# TubesMagangURO.net
KiCad netlist of a schematic drawn in Altium Designer
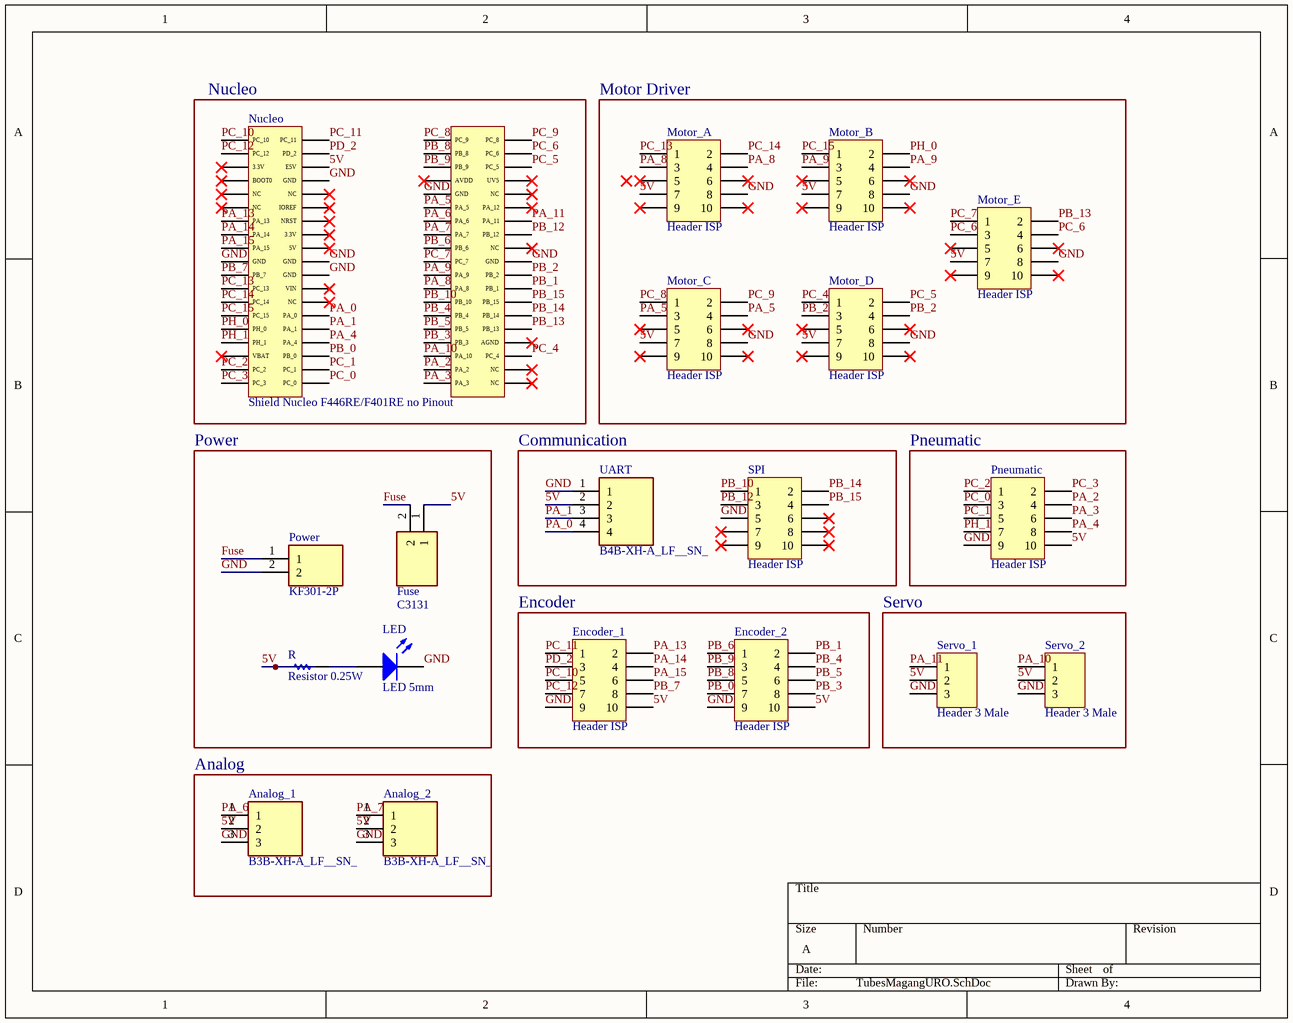
[diagram p0: TubesMagangURO.SchDoc]

(export (version "E")
  (design (tool "Eeschema 10.0.6"))
  (components
    (comp (ref "Analog_1")
      (value "B3B-XH-A_LF__SN_")
      (footprint "B3BXHALFSN")
      (description "Connector")
      (fields (field (name "MANUFACTURER_PART_NUMBER") "B3B-XH-A(LF)(SN)"))
      (libsource (lib "SamacSys") (part "B3B-XH-A_LF__SN_"))
    )
    (comp (ref "Analog_2")
      (value "B3B-XH-A_LF__SN_")
      (footprint "B3BXHALFSN")
      (description "Connector")
      (fields (field (name "MANUFACTURER_PART_NUMBER") "B3B-XH-A(LF)(SN)"))
      (libsource (lib "SamacSys") (part "B3B-XH-A_LF__SN_"))
    )
    (comp (ref "Encoder_1")
      (value "Header ISP")
      (footprint "Header ISP")
      (libsource (lib "GAPlib_CONNECTOR") (part "Header ISP"))
    )
    (comp (ref "Encoder_2")
      (value "Header ISP")
      (footprint "Header ISP")
      (libsource (lib "GAPlib_CONNECTOR") (part "Header ISP"))
    )
    (comp (ref "Fuse")
      (value "C3131")
      (footprint "SamacSys:C3131")
      (description "Undefined or Miscellaneous")
      (libsource (lib "*") (part "C3131"))
    )
    (comp (ref "LED")
      (value "LED 5mm")
      (footprint "LED 5mm")
      (libsource (lib "GAPlib_DEVICES") (part "LED 5mm"))
    )
    (comp (ref "Motor_A")
      (value "Header ISP")
      (footprint "Header ISP")
      (libsource (lib "GAPlib_CONNECTOR") (part "Header ISP"))
    )
    (comp (ref "Motor_B")
      (value "Header ISP")
      (footprint "Header ISP")
      (libsource (lib "GAPlib_CONNECTOR") (part "Header ISP"))
    )
    (comp (ref "Motor_C")
      (value "Header ISP")
      (footprint "Header ISP")
      (libsource (lib "GAPlib_CONNECTOR") (part "Header ISP"))
    )
    (comp (ref "Motor_D")
      (value "Header ISP")
      (footprint "Header ISP")
      (libsource (lib "GAPlib_CONNECTOR") (part "Header ISP"))
    )
    (comp (ref "Motor_E")
      (value "Header ISP")
      (footprint "Header ISP")
      (libsource (lib "GAPlib_CONNECTOR") (part "Header ISP"))
    )
    (comp (ref "Nucleo")
      (value "Shield Nucleo F446RE/F401RE no Pinout")
      (footprint "Shield Nucleo-F446RE/F401RE-tanpaPinOut")
      (description "Tanpa Pinout")
      (libsource (lib "GAPlib_SHIELD") (part "Shield Nucleo-F446RE/F401RE-tanpa Pinout"))
    )
    (comp (ref "Pneumatic")
      (value "Header ISP")
      (footprint "Header ISP")
      (libsource (lib "GAPlib_CONNECTOR") (part "Header ISP"))
    )
    (comp (ref "Power")
      (value "KF301-2P")
      (footprint "KF3012P")
      (description "Connector")
      (libsource (lib "SamacSys") (part "KF301-2P"))
    )
    (comp (ref "R")
      (value "Resistor 0.25W")
      (footprint "Resistor 0.25W")
      (libsource (lib "GAPlib_DEVICES") (part "Resistor 0.25W"))
    )
    (comp (ref "Servo_1")
      (value "Header 3 Male")
      (footprint "Header 3 Male")
      (libsource (lib "GAPlib_CONNECTOR") (part "Header 3 Male"))
    )
    (comp (ref "Servo_2")
      (value "Header 3 Male")
      (footprint "Header 3 Male")
      (libsource (lib "GAPlib_CONNECTOR") (part "Header 3 Male"))
    )
    (comp (ref "SPI")
      (value "Header ISP")
      (footprint "Header ISP")
      (libsource (lib "GAPlib_CONNECTOR") (part "Header ISP"))
    )
    (comp (ref "UART")
      (value "B4B-XH-A_LF__SN_")
      (footprint "SamacSys:B4BXHALFSN")
      (description "Connector")
      (fields (field (name "MANUFACTURER_PART_NUMBER") "B4B-XH-A(LF)(SN)"))
      (libsource (lib "SamacSys") (part "B4B-XH-A_LF__SN_"))
    )
  )
  (nets
    (net (code "1") (name "/5V") (class "Default")
      (node (ref "Analog_1") (pin "2") (pinfunction "2_2") (pintype "passive"))
      (node (ref "Analog_2") (pin "2") (pinfunction "2_2") (pintype "passive"))
      (node (ref "Encoder_1") (pin "10") (pinfunction "10_10") (pintype "passive"))
      (node (ref "Encoder_2") (pin "10") (pinfunction "10_10") (pintype "passive"))
      (node (ref "Fuse") (pin "1") (pinfunction "1_1") (pintype "passive"))
      (node (ref "Motor_A") (pin "7") (pinfunction "7_7") (pintype "passive"))
      (node (ref "Motor_B") (pin "7") (pinfunction "7_7") (pintype "passive"))
      (node (ref "Motor_C") (pin "7") (pinfunction "7_7") (pintype "passive"))
      (node (ref "Motor_D") (pin "7") (pinfunction "7_7") (pintype "passive"))
      (node (ref "Motor_E") (pin "7") (pinfunction "7_7") (pintype "passive"))
      (node (ref "Nucleo") (pin "E5V") (pinfunction "E5V_E5V") (pintype "passive"))
      (node (ref "Pneumatic") (pin "10") (pinfunction "10_10") (pintype "passive"))
      (node (ref "R") (pin "1") (pinfunction "1_1") (pintype "passive"))
      (node (ref "Servo_1") (pin "2") (pinfunction "2_2") (pintype "passive"))
      (node (ref "Servo_2") (pin "2") (pinfunction "2_2") (pintype "passive"))
      (node (ref "UART") (pin "2") (pinfunction "2_2") (pintype "passive"))
    )
    (net (code "2") (name "/Fuse") (class "Default")
      (node (ref "Fuse") (pin "2") (pinfunction "2_2") (pintype "passive"))
      (node (ref "Power") (pin "1") (pinfunction "1_1") (pintype "passive"))
    )
    (net (code "3") (name "/GND") (class "Default")
      (node (ref "Analog_1") (pin "3") (pinfunction "3_3") (pintype "passive"))
      (node (ref "Analog_2") (pin "3") (pinfunction "3_3") (pintype "passive"))
      (node (ref "Encoder_1") (pin "9") (pinfunction "9_9") (pintype "passive"))
      (node (ref "Encoder_2") (pin "9") (pinfunction "9_9") (pintype "passive"))
      (node (ref "LED") (pin "2") (pinfunction "K_2") (pintype "passive"))
      (node (ref "Motor_A") (pin "8") (pinfunction "8_8") (pintype "passive"))
      (node (ref "Motor_B") (pin "8") (pinfunction "8_8") (pintype "passive"))
      (node (ref "Motor_C") (pin "8") (pinfunction "8_8") (pintype "passive"))
      (node (ref "Motor_D") (pin "8") (pinfunction "8_8") (pintype "passive"))
      (node (ref "Motor_E") (pin "8") (pinfunction "8_8") (pintype "passive"))
      (node (ref "Nucleo") (pin "GND") (pinfunction "GND_GND") (pintype "passive"))
      (node (ref "Nucleo") (pin "GND1") (pinfunction "GND_GND1") (pintype "passive"))
      (node (ref "Nucleo") (pin "GND2") (pinfunction "GND_GND2") (pintype "passive"))
      (node (ref "Nucleo") (pin "GND3") (pinfunction "GND_GND3") (pintype "passive"))
      (node (ref "Nucleo") (pin "GND4") (pinfunction "GND_GND4") (pintype "passive"))
      (node (ref "Nucleo") (pin "GND5") (pinfunction "GND_GND5") (pintype "passive"))
      (node (ref "Pneumatic") (pin "9") (pinfunction "9_9") (pintype "passive"))
      (node (ref "Power") (pin "2") (pinfunction "2_2") (pintype "passive"))
      (node (ref "SPI") (pin "5") (pinfunction "5_5") (pintype "passive"))
      (node (ref "Servo_1") (pin "3") (pinfunction "3_3") (pintype "passive"))
      (node (ref "Servo_2") (pin "3") (pinfunction "3_3") (pintype "passive"))
      (node (ref "UART") (pin "1") (pinfunction "1_1") (pintype "passive"))
    )
    (net (code "4") (name "/PA_0") (class "Default")
      (node (ref "Nucleo") (pin "PA_0") (pinfunction "PA_0_PA_0") (pintype "passive"))
      (node (ref "UART") (pin "4") (pinfunction "4_4") (pintype "passive"))
    )
    (net (code "5") (name "/PA_1") (class "Default")
      (node (ref "Nucleo") (pin "PA_1") (pinfunction "PA_1_PA_1") (pintype "passive"))
      (node (ref "UART") (pin "3") (pinfunction "3_3") (pintype "passive"))
    )
    (net (code "6") (name "/PA_2") (class "Default")
      (node (ref "Nucleo") (pin "PA_2") (pinfunction "PA_2_PA_2") (pintype "passive"))
      (node (ref "Pneumatic") (pin "4") (pinfunction "4_4") (pintype "passive"))
    )
    (net (code "7") (name "/PA_3") (class "Default")
      (node (ref "Nucleo") (pin "PA_3") (pinfunction "PA_3_PA_3") (pintype "passive"))
      (node (ref "Pneumatic") (pin "6") (pinfunction "6_6") (pintype "passive"))
    )
    (net (code "8") (name "/PA_4") (class "Default")
      (node (ref "Nucleo") (pin "PA_4") (pinfunction "PA_4_PA_4") (pintype "passive"))
      (node (ref "Pneumatic") (pin "8") (pinfunction "8_8") (pintype "passive"))
    )
    (net (code "9") (name "/PA_5") (class "Default")
      (node (ref "Motor_C") (pin "3") (pinfunction "3_3") (pintype "passive"))
      (node (ref "Motor_C") (pin "4") (pinfunction "4_4") (pintype "passive"))
      (node (ref "Nucleo") (pin "PA_5") (pinfunction "PA_5_PA_5") (pintype "passive"))
    )
    (net (code "10") (name "/PA_6") (class "Default")
      (node (ref "Analog_1") (pin "1") (pinfunction "1_1") (pintype "passive"))
      (node (ref "Nucleo") (pin "PA_6") (pinfunction "PA_6_PA_6") (pintype "passive"))
    )
    (net (code "11") (name "/PA_7") (class "Default")
      (node (ref "Analog_2") (pin "1") (pinfunction "1_1") (pintype "passive"))
      (node (ref "Nucleo") (pin "PA_7") (pinfunction "PA_7_PA_7") (pintype "passive"))
    )
    (net (code "12") (name "/PA_8") (class "Default")
      (node (ref "Motor_A") (pin "3") (pinfunction "3_3") (pintype "passive"))
      (node (ref "Motor_A") (pin "4") (pinfunction "4_4") (pintype "passive"))
      (node (ref "Nucleo") (pin "PA_8") (pinfunction "PA_8_PA_8") (pintype "passive"))
    )
    (net (code "13") (name "/PA_9") (class "Default")
      (node (ref "Motor_B") (pin "3") (pinfunction "3_3") (pintype "passive"))
      (node (ref "Motor_B") (pin "4") (pinfunction "4_4") (pintype "passive"))
      (node (ref "Nucleo") (pin "PA_9") (pinfunction "PA_9_PA_9") (pintype "passive"))
    )
    (net (code "14") (name "/PA_10") (class "Default")
      (node (ref "Nucleo") (pin "PA_10") (pinfunction "PA_10_PA_10") (pintype "passive"))
      (node (ref "Servo_2") (pin "1") (pinfunction "1_1") (pintype "passive"))
    )
    (net (code "15") (name "/PA_11") (class "Default")
      (node (ref "Nucleo") (pin "PA_11") (pinfunction "PA_11_PA_11") (pintype "passive"))
      (node (ref "Servo_1") (pin "1") (pinfunction "1_1") (pintype "passive"))
    )
    (net (code "16") (name "/PA_13") (class "Default")
      (node (ref "Encoder_1") (pin "2") (pinfunction "2_2") (pintype "passive"))
      (node (ref "Nucleo") (pin "PA_13") (pinfunction "PA_13_PA_13") (pintype "passive"))
    )
    (net (code "17") (name "/PA_14") (class "Default")
      (node (ref "Encoder_1") (pin "4") (pinfunction "4_4") (pintype "passive"))
      (node (ref "Nucleo") (pin "PA_14") (pinfunction "PA_14_PA_14") (pintype "passive"))
    )
    (net (code "18") (name "/PA_15") (class "Default")
      (node (ref "Encoder_1") (pin "6") (pinfunction "6_6") (pintype "passive"))
      (node (ref "Nucleo") (pin "PA_15") (pinfunction "PA_15_PA_15") (pintype "passive"))
    )
    (net (code "19") (name "/PB_0") (class "Default")
      (node (ref "Encoder_2") (pin "7") (pinfunction "7_7") (pintype "passive"))
      (node (ref "Nucleo") (pin "PB_0") (pinfunction "PB_0_PB_0") (pintype "passive"))
    )
    (net (code "20") (name "/PB_1") (class "Default")
      (node (ref "Encoder_2") (pin "2") (pinfunction "2_2") (pintype "passive"))
      (node (ref "Nucleo") (pin "PB_1") (pinfunction "PB_1_PB_1") (pintype "passive"))
    )
    (net (code "21") (name "/PB_2") (class "Default")
      (node (ref "Motor_D") (pin "3") (pinfunction "3_3") (pintype "passive"))
      (node (ref "Motor_D") (pin "4") (pinfunction "4_4") (pintype "passive"))
      (node (ref "Nucleo") (pin "PB_2") (pinfunction "PB_2_PB_2") (pintype "passive"))
    )
    (net (code "22") (name "/PB_3") (class "Default")
      (node (ref "Encoder_2") (pin "8") (pinfunction "8_8") (pintype "passive"))
      (node (ref "Nucleo") (pin "PB_3") (pinfunction "PB_3_PB_3") (pintype "passive"))
    )
    (net (code "23") (name "/PB_4") (class "Default")
      (node (ref "Encoder_2") (pin "4") (pinfunction "4_4") (pintype "passive"))
      (node (ref "Nucleo") (pin "PB_4") (pinfunction "PB_4_PB_4") (pintype "passive"))
    )
    (net (code "24") (name "/PB_5") (class "Default")
      (node (ref "Encoder_2") (pin "6") (pinfunction "6_6") (pintype "passive"))
      (node (ref "Nucleo") (pin "PB_5") (pinfunction "PB_5_PB_5") (pintype "passive"))
    )
    (net (code "25") (name "/PB_6") (class "Default")
      (node (ref "Encoder_2") (pin "1") (pinfunction "1_1") (pintype "passive"))
      (node (ref "Nucleo") (pin "PB_6") (pinfunction "PB_6_PB_6") (pintype "passive"))
    )
    (net (code "26") (name "/PB_7") (class "Default")
      (node (ref "Encoder_1") (pin "8") (pinfunction "8_8") (pintype "passive"))
      (node (ref "Nucleo") (pin "PB_7") (pinfunction "PB_7_PB_7") (pintype "passive"))
    )
    (net (code "27") (name "/PB_8") (class "Default")
      (node (ref "Encoder_2") (pin "5") (pinfunction "5_5") (pintype "passive"))
      (node (ref "Nucleo") (pin "PB_8") (pinfunction "PB_8_PB_8") (pintype "passive"))
    )
    (net (code "28") (name "/PB_9") (class "Default")
      (node (ref "Encoder_2") (pin "3") (pinfunction "3_3") (pintype "passive"))
      (node (ref "Nucleo") (pin "PB_9") (pinfunction "PB_9_PB_9") (pintype "passive"))
    )
    (net (code "29") (name "/PB_10") (class "Default")
      (node (ref "Nucleo") (pin "PB_10") (pinfunction "PB_10_PB_10") (pintype "passive"))
      (node (ref "SPI") (pin "1") (pinfunction "1_1") (pintype "passive"))
    )
    (net (code "30") (name "/PB_12") (class "Default")
      (node (ref "Nucleo") (pin "PB_12") (pinfunction "PB_12_PB_12") (pintype "passive"))
      (node (ref "SPI") (pin "3") (pinfunction "3_3") (pintype "passive"))
    )
    (net (code "31") (name "/PB_13") (class "Default")
      (node (ref "Motor_E") (pin "2") (pinfunction "2_2") (pintype "passive"))
      (node (ref "Nucleo") (pin "PB_13") (pinfunction "PB_13_PB_13") (pintype "passive"))
    )
    (net (code "32") (name "/PB_14") (class "Default")
      (node (ref "Nucleo") (pin "PB_14") (pinfunction "PB_14_PB_14") (pintype "passive"))
      (node (ref "SPI") (pin "2") (pinfunction "2_2") (pintype "passive"))
    )
    (net (code "33") (name "/PB_15") (class "Default")
      (node (ref "Nucleo") (pin "PB_15") (pinfunction "PB_15_PB_15") (pintype "passive"))
      (node (ref "SPI") (pin "4") (pinfunction "4_4") (pintype "passive"))
    )
    (net (code "34") (name "/PC_0") (class "Default")
      (node (ref "Nucleo") (pin "PC_0") (pinfunction "PC_0_PC_0") (pintype "passive"))
      (node (ref "Pneumatic") (pin "3") (pinfunction "3_3") (pintype "passive"))
    )
    (net (code "35") (name "/PC_1") (class "Default")
      (node (ref "Nucleo") (pin "PC_1") (pinfunction "PC_1_PC_1") (pintype "passive"))
      (node (ref "Pneumatic") (pin "5") (pinfunction "5_5") (pintype "passive"))
    )
    (net (code "36") (name "/PC_2") (class "Default")
      (node (ref "Nucleo") (pin "PC_2") (pinfunction "PC_2_PC_2") (pintype "passive"))
      (node (ref "Pneumatic") (pin "1") (pinfunction "1_1") (pintype "passive"))
    )
    (net (code "37") (name "/PC_3") (class "Default")
      (node (ref "Nucleo") (pin "PC_3") (pinfunction "PC_3_PC_3") (pintype "passive"))
      (node (ref "Pneumatic") (pin "2") (pinfunction "2_2") (pintype "passive"))
    )
    (net (code "38") (name "/PC_4") (class "Default")
      (node (ref "Motor_D") (pin "1") (pinfunction "1_1") (pintype "passive"))
      (node (ref "Nucleo") (pin "PC_4") (pinfunction "PC_4_PC_4") (pintype "passive"))
    )
    (net (code "39") (name "/PC_5") (class "Default")
      (node (ref "Motor_D") (pin "2") (pinfunction "2_2") (pintype "passive"))
      (node (ref "Nucleo") (pin "PC_5") (pinfunction "PC_5_PC_5") (pintype "passive"))
    )
    (net (code "40") (name "/PC_6") (class "Default")
      (node (ref "Motor_E") (pin "3") (pinfunction "3_3") (pintype "passive"))
      (node (ref "Motor_E") (pin "4") (pinfunction "4_4") (pintype "passive"))
      (node (ref "Nucleo") (pin "PC_6") (pinfunction "PC_6_PC_6") (pintype "passive"))
    )
    (net (code "41") (name "/PC_7") (class "Default")
      (node (ref "Motor_E") (pin "1") (pinfunction "1_1") (pintype "passive"))
      (node (ref "Nucleo") (pin "PC_7") (pinfunction "PC_7_PC_7") (pintype "passive"))
    )
    (net (code "42") (name "/PC_8") (class "Default")
      (node (ref "Motor_C") (pin "1") (pinfunction "1_1") (pintype "passive"))
      (node (ref "Nucleo") (pin "PC_9") (pinfunction "PC_9_PC_9") (pintype "passive"))
    )
    (net (code "43") (name "/PC_9") (class "Default")
      (node (ref "Motor_C") (pin "2") (pinfunction "2_2") (pintype "passive"))
      (node (ref "Nucleo") (pin "PC_8") (pinfunction "PC_8_PC_8") (pintype "passive"))
    )
    (net (code "44") (name "/PC_10") (class "Default")
      (node (ref "Encoder_1") (pin "5") (pinfunction "5_5") (pintype "passive"))
      (node (ref "Nucleo") (pin "PC_10") (pinfunction "PC_10_PC_10") (pintype "passive"))
    )
    (net (code "45") (name "/PC_11") (class "Default")
      (node (ref "Encoder_1") (pin "1") (pinfunction "1_1") (pintype "passive"))
      (node (ref "Nucleo") (pin "PC_11") (pinfunction "PC_11_PC_11") (pintype "passive"))
    )
    (net (code "46") (name "/PC_12") (class "Default")
      (node (ref "Encoder_1") (pin "7") (pinfunction "7_7") (pintype "passive"))
      (node (ref "Nucleo") (pin "PC_12") (pinfunction "PC_12_PC_12") (pintype "passive"))
    )
    (net (code "47") (name "/PC_13") (class "Default")
      (node (ref "Motor_A") (pin "1") (pinfunction "1_1") (pintype "passive"))
      (node (ref "Nucleo") (pin "PC_13") (pinfunction "PC_13_PC_13") (pintype "passive"))
    )
    (net (code "48") (name "/PC_14") (class "Default")
      (node (ref "Motor_A") (pin "2") (pinfunction "2_2") (pintype "passive"))
      (node (ref "Nucleo") (pin "PC_14") (pinfunction "PC_14_PC_14") (pintype "passive"))
    )
    (net (code "49") (name "/PC_15") (class "Default")
      (node (ref "Motor_B") (pin "1") (pinfunction "1_1") (pintype "passive"))
      (node (ref "Nucleo") (pin "PC_15") (pinfunction "PC_15_PC_15") (pintype "passive"))
    )
    (net (code "50") (name "/PD_2") (class "Default")
      (node (ref "Encoder_1") (pin "3") (pinfunction "3_3") (pintype "passive"))
      (node (ref "Nucleo") (pin "PD_2") (pinfunction "PD_2_PD_2") (pintype "passive"))
    )
    (net (code "51") (name "/PH_0") (class "Default")
      (node (ref "Motor_B") (pin "2") (pinfunction "2_2") (pintype "passive"))
      (node (ref "Nucleo") (pin "PH_0") (pinfunction "PH_0_PH_0") (pintype "passive"))
    )
    (net (code "52") (name "/PH_1") (class "Default")
      (node (ref "Nucleo") (pin "PH_1") (pinfunction "PH_1_PH_1") (pintype "passive"))
      (node (ref "Pneumatic") (pin "7") (pinfunction "7_7") (pintype "passive"))
    )
    (net (code "53") (name "Net-(LED-A)") (class "Default")
      (node (ref "LED") (pin "1") (pinfunction "A_1") (pintype "passive"))
      (node (ref "R") (pin "2") (pinfunction "2_2") (pintype "passive"))
    )
    (net (code "54") (name "unconnected-(Motor_A-Pad5)") (class "Default")
      (node (ref "Motor_A") (pin "5") (pinfunction "5_5") (pintype "passive+no_connect"))
    )
    (net (code "55") (name "unconnected-(Motor_A-Pad6)") (class "Default")
      (node (ref "Motor_A") (pin "6") (pinfunction "6_6") (pintype "passive+no_connect"))
    )
    (net (code "56") (name "unconnected-(Motor_A-Pad9)") (class "Default")
      (node (ref "Motor_A") (pin "9") (pinfunction "9_9") (pintype "passive+no_connect"))
    )
    (net (code "57") (name "unconnected-(Motor_A-Pad10)") (class "Default")
      (node (ref "Motor_A") (pin "10") (pinfunction "10_10") (pintype "passive+no_connect"))
    )
    (net (code "58") (name "unconnected-(Motor_B-Pad5)") (class "Default")
      (node (ref "Motor_B") (pin "5") (pinfunction "5_5") (pintype "passive+no_connect"))
    )
    (net (code "59") (name "unconnected-(Motor_B-Pad6)") (class "Default")
      (node (ref "Motor_B") (pin "6") (pinfunction "6_6") (pintype "passive+no_connect"))
    )
    (net (code "60") (name "unconnected-(Motor_B-Pad9)") (class "Default")
      (node (ref "Motor_B") (pin "9") (pinfunction "9_9") (pintype "passive+no_connect"))
    )
    (net (code "61") (name "unconnected-(Motor_B-Pad10)") (class "Default")
      (node (ref "Motor_B") (pin "10") (pinfunction "10_10") (pintype "passive+no_connect"))
    )
    (net (code "62") (name "unconnected-(Motor_C-Pad5)") (class "Default")
      (node (ref "Motor_C") (pin "5") (pinfunction "5_5") (pintype "passive+no_connect"))
    )
    (net (code "63") (name "unconnected-(Motor_C-Pad6)") (class "Default")
      (node (ref "Motor_C") (pin "6") (pinfunction "6_6") (pintype "passive+no_connect"))
    )
    (net (code "64") (name "unconnected-(Motor_C-Pad9)") (class "Default")
      (node (ref "Motor_C") (pin "9") (pinfunction "9_9") (pintype "passive+no_connect"))
    )
    (net (code "65") (name "unconnected-(Motor_C-Pad10)") (class "Default")
      (node (ref "Motor_C") (pin "10") (pinfunction "10_10") (pintype "passive+no_connect"))
    )
    (net (code "66") (name "unconnected-(Motor_D-Pad5)") (class "Default")
      (node (ref "Motor_D") (pin "5") (pinfunction "5_5") (pintype "passive+no_connect"))
    )
    (net (code "67") (name "unconnected-(Motor_D-Pad6)") (class "Default")
      (node (ref "Motor_D") (pin "6") (pinfunction "6_6") (pintype "passive+no_connect"))
    )
    (net (code "68") (name "unconnected-(Motor_D-Pad9)") (class "Default")
      (node (ref "Motor_D") (pin "9") (pinfunction "9_9") (pintype "passive+no_connect"))
    )
    (net (code "69") (name "unconnected-(Motor_D-Pad10)") (class "Default")
      (node (ref "Motor_D") (pin "10") (pinfunction "10_10") (pintype "passive+no_connect"))
    )
    (net (code "70") (name "unconnected-(Motor_E-Pad5)") (class "Default")
      (node (ref "Motor_E") (pin "5") (pinfunction "5_5") (pintype "passive+no_connect"))
    )
    (net (code "71") (name "unconnected-(Motor_E-Pad6)") (class "Default")
      (node (ref "Motor_E") (pin "6") (pinfunction "6_6") (pintype "passive+no_connect"))
    )
    (net (code "72") (name "unconnected-(Motor_E-Pad9)") (class "Default")
      (node (ref "Motor_E") (pin "9") (pinfunction "9_9") (pintype "passive+no_connect"))
    )
    (net (code "73") (name "unconnected-(Motor_E-Pad10)") (class "Default")
      (node (ref "Motor_E") (pin "10") (pinfunction "10_10") (pintype "passive+no_connect"))
    )
    (net (code "74") (name "unconnected-(Nucleo-3.3V-Pad3V3)") (class "Default")
      (node (ref "Nucleo") (pin "3V3") (pinfunction "3.3V_3V3") (pintype "passive+no_connect"))
    )
    (net (code "75") (name "unconnected-(Nucleo-NC-PadNC1)") (class "Default")
      (node (ref "Nucleo") (pin "NC1") (pinfunction "NC_NC1") (pintype "passive+no_connect"))
    )
    (net (code "76") (name "unconnected-(Nucleo-NC-PadNC2)") (class "Default")
      (node (ref "Nucleo") (pin "NC2") (pinfunction "NC_NC2") (pintype "passive+no_connect"))
    )
    (net (code "77") (name "unconnected-(Nucleo-NC-PadNC3)") (class "Default")
      (node (ref "Nucleo") (pin "NC3") (pinfunction "NC_NC3") (pintype "passive+no_connect"))
    )
    (net (code "78") (name "unconnected-(Nucleo-NC-PadNC4)") (class "Default")
      (node (ref "Nucleo") (pin "NC4") (pinfunction "NC_NC4") (pintype "passive+no_connect"))
    )
    (net (code "79") (name "unconnected-(Nucleo-NC-PadNC5)") (class "Default")
      (node (ref "Nucleo") (pin "NC5") (pinfunction "NC_NC5") (pintype "passive+no_connect"))
    )
    (net (code "80") (name "unconnected-(Nucleo-NC-PadNC6)") (class "Default")
      (node (ref "Nucleo") (pin "NC6") (pinfunction "NC_NC6") (pintype "passive+no_connect"))
    )
    (net (code "81") (name "unconnected-(Nucleo-NC-PadNC7)") (class "Default")
      (node (ref "Nucleo") (pin "NC7") (pinfunction "NC_NC7") (pintype "passive+no_connect"))
    )
    (net (code "82") (name "unconnected-(Nucleo-NC-PadNC8)") (class "Default")
      (node (ref "Nucleo") (pin "NC8") (pinfunction "NC_NC8") (pintype "passive+no_connect"))
    )
    (net (code "83") (name "unconnected-(Nucleo-Pad3.3V)") (class "Default")
      (node (ref "Nucleo") (pin "3.3V") (pinfunction "3.3V_3.3V") (pintype "passive+no_connect"))
    )
    (net (code "84") (name "unconnected-(Nucleo-Pad5V)") (class "Default")
      (node (ref "Nucleo") (pin "5V") (pinfunction "5V_5V") (pintype "passive+no_connect"))
    )
    (net (code "85") (name "unconnected-(Nucleo-PadAGND)") (class "Default")
      (node (ref "Nucleo") (pin "AGND") (pinfunction "AGND_AGND") (pintype "passive+no_connect"))
    )
    (net (code "86") (name "unconnected-(Nucleo-PadAVDD)") (class "Default")
      (node (ref "Nucleo") (pin "AVDD") (pinfunction "AVDD_AVDD") (pintype "passive+no_connect"))
    )
    (net (code "87") (name "unconnected-(Nucleo-PadBOOT0)") (class "Default")
      (node (ref "Nucleo") (pin "BOOT0") (pinfunction "BOOT0_BOOT0") (pintype "passive+no_connect"))
    )
    (net (code "88") (name "unconnected-(Nucleo-PadIOREF)") (class "Default")
      (node (ref "Nucleo") (pin "IOREF") (pinfunction "IOREF_IOREF") (pintype "passive+no_connect"))
    )
    (net (code "89") (name "unconnected-(Nucleo-PadNRST)") (class "Default")
      (node (ref "Nucleo") (pin "NRST") (pinfunction "NRST_NRST") (pintype "passive+no_connect"))
    )
    (net (code "90") (name "unconnected-(Nucleo-PadPA_12)") (class "Default")
      (node (ref "Nucleo") (pin "PA_12") (pinfunction "PA_12_PA_12") (pintype "passive+no_connect"))
    )
    (net (code "91") (name "unconnected-(Nucleo-PadUV5)") (class "Default")
      (node (ref "Nucleo") (pin "UV5") (pinfunction "UV5_UV5") (pintype "passive+no_connect"))
    )
    (net (code "92") (name "unconnected-(Nucleo-PadVBAT)") (class "Default")
      (node (ref "Nucleo") (pin "VBAT") (pinfunction "VBAT_VBAT") (pintype "passive+no_connect"))
    )
    (net (code "93") (name "unconnected-(Nucleo-PadVIN)") (class "Default")
      (node (ref "Nucleo") (pin "VIN") (pinfunction "VIN_VIN") (pintype "passive+no_connect"))
    )
    (net (code "94") (name "unconnected-(SPI-Pad6)") (class "Default")
      (node (ref "SPI") (pin "6") (pinfunction "6_6") (pintype "passive+no_connect"))
    )
    (net (code "95") (name "unconnected-(SPI-Pad7)") (class "Default")
      (node (ref "SPI") (pin "7") (pinfunction "7_7") (pintype "passive+no_connect"))
    )
    (net (code "96") (name "unconnected-(SPI-Pad8)") (class "Default")
      (node (ref "SPI") (pin "8") (pinfunction "8_8") (pintype "passive+no_connect"))
    )
    (net (code "97") (name "unconnected-(SPI-Pad9)") (class "Default")
      (node (ref "SPI") (pin "9") (pinfunction "9_9") (pintype "passive+no_connect"))
    )
    (net (code "98") (name "unconnected-(SPI-Pad10)") (class "Default")
      (node (ref "SPI") (pin "10") (pinfunction "10_10") (pintype "passive+no_connect"))
    )
  )
)
